# fanmonitor.net
KiCad netlist of a schematic drawn in EAGLE
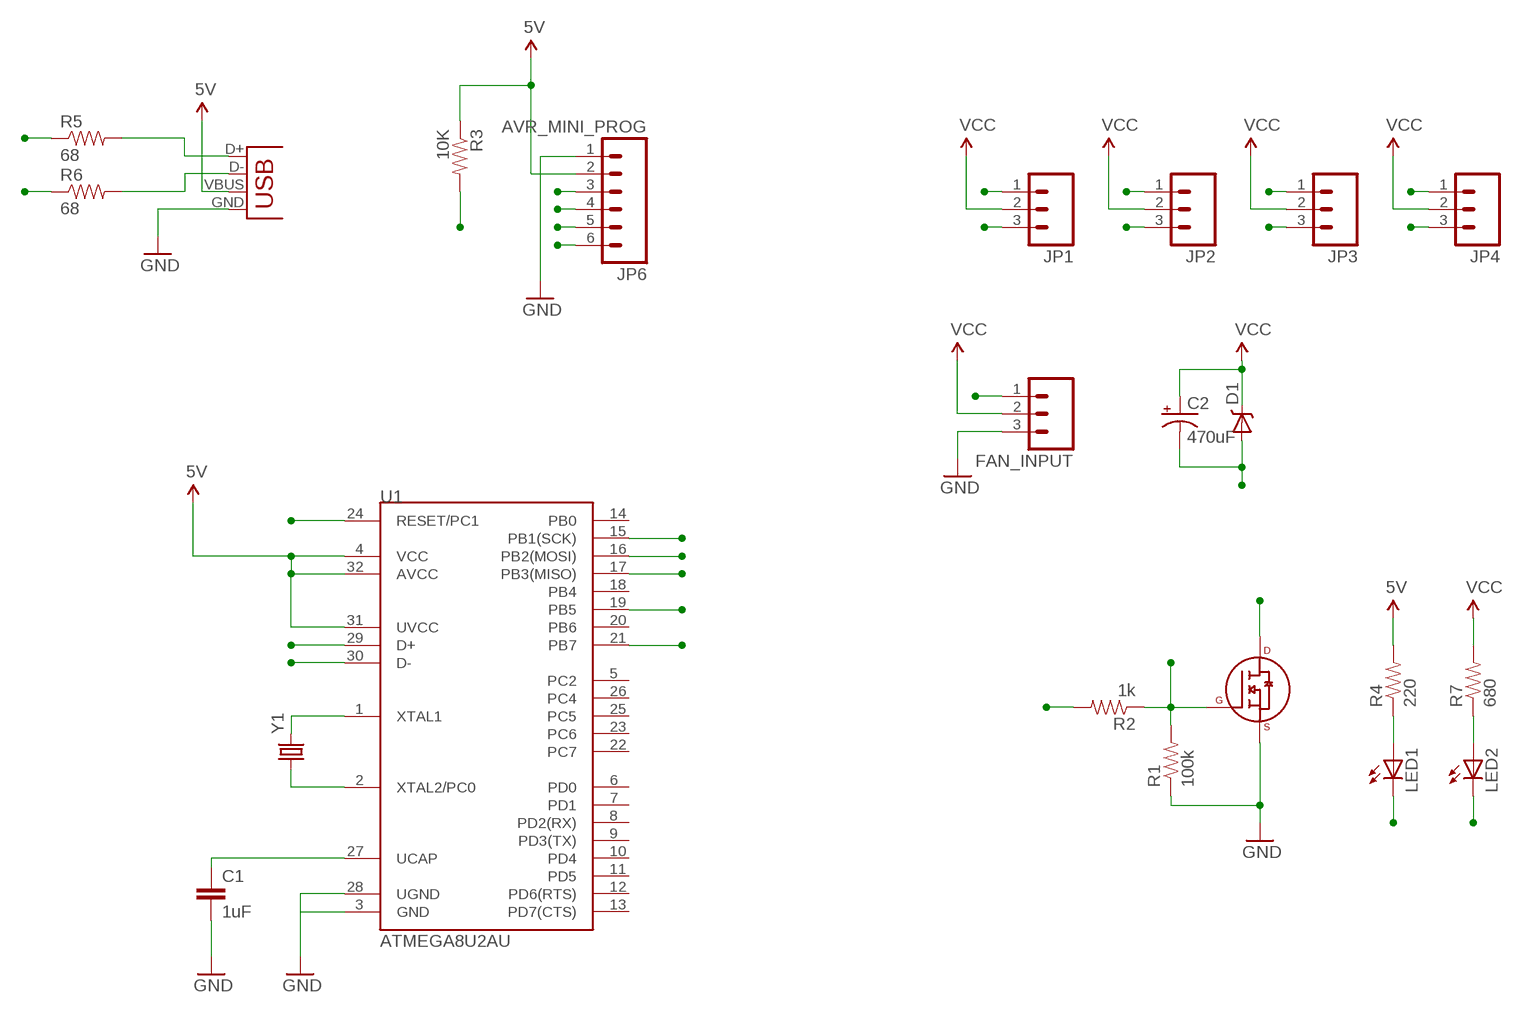
[diagram p0: schematic, sheet 1]

(export (version "E")
  (design (tool "Eeschema 10.0.6"))
  (components
    (comp (ref "C1")
      (value "1uF")
      (footprint "eagle-import:0603-CAP")
      (libsource (lib "eagle-import") (part "CAP0603-CAP"))
    )
    (comp (ref "C2")
      (value "470uF")
      (footprint "eagle-import:PANASONIC_D")
      (libsource (lib "eagle-import") (part "CAP_POLD"))
    )
    (comp (ref "D1")
      (value "DIODE-SCHOTTKY_")
      (footprint "eagle-import:SMA-DIODE")
      (libsource (lib "eagle-import") (part "DIODE-SCHOTTKY_"))
    )
    (comp (ref "FAN_INPUT")
      (value "M03PTH")
      (footprint "eagle-import:1X03")
      (libsource (lib "eagle-import") (part "M03PTH"))
    )
    (comp (ref "JP1")
      (value "M03PTH")
      (footprint "eagle-import:1X03")
      (libsource (lib "eagle-import") (part "M03PTH"))
    )
    (comp (ref "JP2")
      (value "M03PTH")
      (footprint "eagle-import:1X03")
      (libsource (lib "eagle-import") (part "M03PTH"))
    )
    (comp (ref "JP3")
      (value "M03PTH")
      (footprint "eagle-import:1X03")
      (libsource (lib "eagle-import") (part "M03PTH"))
    )
    (comp (ref "JP4")
      (value "M03PTH")
      (footprint "eagle-import:1X03")
      (libsource (lib "eagle-import") (part "M03PTH"))
    )
    (comp (ref "JP6")
      (value "AVR_MINI_PROG")
      (footprint "eagle-import:1X06")
      (libsource (lib "eagle-import") (part "M06SIP"))
    )
    (comp (ref "LED1")
      (value "LED0603")
      (footprint "eagle-import:LED-0603")
      (libsource (lib "eagle-import") (part "LED0603"))
    )
    (comp (ref "LED2")
      (value "LED0603")
      (footprint "eagle-import:LED-0603")
      (libsource (lib "eagle-import") (part "LED0603"))
    )
    (comp (ref "R1")
      (value "100k")
      (footprint "eagle-import:0603-RES")
      (libsource (lib "eagle-import") (part "RESISTOR0603-RES"))
    )
    (comp (ref "R2")
      (value "1k")
      (footprint "eagle-import:0603-RES")
      (libsource (lib "eagle-import") (part "RESISTOR0603-RES"))
    )
    (comp (ref "R3")
      (value "10K")
      (footprint "eagle-import:0603-RES")
      (libsource (lib "eagle-import") (part "RESISTOR0603-RES"))
    )
    (comp (ref "R4")
      (value "220")
      (footprint "eagle-import:0603-RES")
      (libsource (lib "eagle-import") (part "RESISTOR0603-RES"))
    )
    (comp (ref "R5")
      (value "68")
      (footprint "eagle-import:0603-RES")
      (libsource (lib "eagle-import") (part "RESISTOR0603-RES"))
    )
    (comp (ref "R6")
      (value "68")
      (footprint "eagle-import:0603-RES")
      (libsource (lib "eagle-import") (part "RESISTOR0603-RES"))
    )
    (comp (ref "R7")
      (value "680")
      (footprint "eagle-import:0603-RES")
      (libsource (lib "eagle-import") (part "RESISTOR0603-RES"))
    )
    (comp (ref "U$4")
      (value "RFD14N05L")
      (footprint "eagle-import:TO-252AA")
      (libsource (lib "eagle-import") (part "RFD14N05L"))
    )
    (comp (ref "U1")
      (value "ATMEGA8U2AU")
      (footprint "eagle-import:TQFP32-08")
      (libsource (lib "eagle-import") (part "ATMEGA8U2AU"))
    )
    (comp (ref "X1")
      (value "USBSMD")
      (footprint "eagle-import:USB-MINIB")
      (libsource (lib "eagle-import") (part "USBSMD"))
    )
    (comp (ref "Y1")
      (value "CRYSTAL5X3")
      (footprint "eagle-import:CRYSTAL-SMD-5X3")
      (libsource (lib "eagle-import") (part "CRYSTAL5X3"))
    )
  )
  (nets
    (net (code "1") (name "/D+") (class "Default")
      (node (ref "R5") (pin "1") (pinfunction "1_1") (pintype "passive"))
      (node (ref "U1") (pin "29") (pinfunction "D+_29") (pintype "bidirectional"))
    )
    (net (code "2") (name "/D-") (class "Default")
      (node (ref "R6") (pin "1") (pinfunction "1_1") (pintype "passive"))
      (node (ref "U1") (pin "30") (pinfunction "D-_30") (pintype "bidirectional"))
    )
    (net (code "3") (name "/MISO") (class "Default")
      (node (ref "JP6") (pin "3") (pinfunction "3_3") (pintype "passive"))
      (node (ref "U1") (pin "17") (pinfunction "PB3(MISO)_17") (pintype "bidirectional"))
    )
    (net (code "4") (name "/MOSI") (class "Default")
      (node (ref "JP6") (pin "6") (pinfunction "6_6") (pintype "passive"))
      (node (ref "U1") (pin "16") (pinfunction "PB2(MOSI)_16") (pintype "bidirectional"))
    )
    (net (code "5") (name "/PWM") (class "Default")
      (node (ref "FAN_INPUT") (pin "1") (pinfunction "1_1") (pintype "passive"))
      (node (ref "R2") (pin "2") (pinfunction "2_2") (pintype "passive"))
      (node (ref "U1") (pin "21") (pinfunction "PB7_21") (pintype "bidirectional"))
    )
    (net (code "6") (name "/PWM_OUT") (class "Default")
      (node (ref "C2") (pin "-") (pinfunction "-_-") (pintype "passive"))
      (node (ref "D1") (pin "A") (pinfunction "A_A") (pintype "passive"))
      (node (ref "JP1") (pin "3") (pinfunction "3_3") (pintype "passive"))
      (node (ref "JP2") (pin "3") (pinfunction "3_3") (pintype "passive"))
      (node (ref "JP3") (pin "3") (pinfunction "3_3") (pintype "passive"))
      (node (ref "JP4") (pin "3") (pinfunction "3_3") (pintype "passive"))
      (node (ref "LED2") (pin "C") (pinfunction "C_C") (pintype "passive"))
      (node (ref "U$4") (pin "4") (pinfunction "D_4") (pintype "bidirectional"))
    )
    (net (code "7") (name "/SCK") (class "Default")
      (node (ref "JP6") (pin "4") (pinfunction "4_4") (pintype "passive"))
      (node (ref "U1") (pin "15") (pinfunction "PB1(SCK)_15") (pintype "bidirectional"))
    )
    (net (code "8") (name "/STAT") (class "Default")
      (node (ref "LED1") (pin "C") (pinfunction "C_C") (pintype "passive"))
      (node (ref "U1") (pin "19") (pinfunction "PB5_19") (pintype "bidirectional"))
    )
    (net (code "9") (name "/{slash}RST") (class "Default")
      (node (ref "JP6") (pin "5") (pinfunction "5_5") (pintype "passive"))
      (node (ref "R3") (pin "2") (pinfunction "2_2") (pintype "passive"))
      (node (ref "U1") (pin "24") (pinfunction "RESET/PC1_24") (pintype "bidirectional"))
    )
    (net (code "10") (name "5V") (class "Default")
      (node (ref "JP6") (pin "2") (pinfunction "2_2") (pintype "passive"))
      (node (ref "R3") (pin "1") (pinfunction "1_1") (pintype "passive"))
      (node (ref "R4") (pin "2") (pinfunction "2_2") (pintype "passive"))
      (node (ref "U1") (pin "31") (pinfunction "UVCC_31") (pintype "bidirectional"))
      (node (ref "U1") (pin "32") (pinfunction "AVCC_32") (pintype "bidirectional"))
      (node (ref "U1") (pin "4") (pinfunction "VCC_4") (pintype "bidirectional"))
      (node (ref "X1") (pin "VBUS") (pinfunction "VBUS_VBUS") (pintype "bidirectional"))
    )
    (net (code "11") (name "GND") (class "Default")
      (node (ref "C1") (pin "2") (pinfunction "2_2") (pintype "passive"))
      (node (ref "FAN_INPUT") (pin "3") (pinfunction "3_3") (pintype "passive"))
      (node (ref "JP1") (pin "1") (pinfunction "1_1") (pintype "passive"))
      (node (ref "JP2") (pin "1") (pinfunction "1_1") (pintype "passive"))
      (node (ref "JP3") (pin "1") (pinfunction "1_1") (pintype "passive"))
      (node (ref "JP4") (pin "1") (pinfunction "1_1") (pintype "passive"))
      (node (ref "JP6") (pin "1") (pinfunction "1_1") (pintype "passive"))
      (node (ref "R1") (pin "1") (pinfunction "1_1") (pintype "passive"))
      (node (ref "U$4") (pin "3") (pinfunction "S_3") (pintype "bidirectional"))
      (node (ref "U1") (pin "28") (pinfunction "UGND_28") (pintype "bidirectional"))
      (node (ref "U1") (pin "3") (pinfunction "GND_3") (pintype "bidirectional"))
      (node (ref "X1") (pin "GND") (pinfunction "GND_GND") (pintype "bidirectional"))
    )
    (net (code "12") (name "Net-(LED1-PadA)") (class "Default")
      (node (ref "LED1") (pin "A") (pinfunction "A_A") (pintype "passive"))
      (node (ref "R4") (pin "1") (pinfunction "1_1") (pintype "passive"))
    )
    (net (code "13") (name "Net-(LED2-PadA)") (class "Default")
      (node (ref "LED2") (pin "A") (pinfunction "A_A") (pintype "passive"))
      (node (ref "R7") (pin "1") (pinfunction "1_1") (pintype "passive"))
    )
    (net (code "14") (name "Net-(R5-Pad2)") (class "Default")
      (node (ref "R5") (pin "2") (pinfunction "2_2") (pintype "passive"))
      (node (ref "X1") (pin "D+") (pinfunction "D+_D+") (pintype "bidirectional"))
    )
    (net (code "15") (name "Net-(R6-Pad2)") (class "Default")
      (node (ref "R6") (pin "2") (pinfunction "2_2") (pintype "passive"))
      (node (ref "X1") (pin "D-") (pinfunction "D-_D-") (pintype "bidirectional"))
    )
    (net (code "16") (name "Net-(U$4-G)") (class "Default")
      (node (ref "R1") (pin "2") (pinfunction "2_2") (pintype "passive"))
      (node (ref "R2") (pin "1") (pinfunction "1_1") (pintype "passive"))
      (node (ref "U$4") (pin "1") (pinfunction "G_1") (pintype "bidirectional"))
    )
    (net (code "17") (name "Net-(U1-UCAP)") (class "Default")
      (node (ref "C1") (pin "1") (pinfunction "1_1") (pintype "passive"))
      (node (ref "U1") (pin "27") (pinfunction "UCAP_27") (pintype "bidirectional"))
    )
    (net (code "18") (name "Net-(U1-XTAL1)") (class "Default")
      (node (ref "U1") (pin "1") (pinfunction "XTAL1_1") (pintype "bidirectional"))
      (node (ref "Y1") (pin "3") (pinfunction "2_3") (pintype "passive"))
    )
    (net (code "19") (name "Net-(U1-XTAL2{slash}PC0)") (class "Default")
      (node (ref "U1") (pin "2") (pinfunction "XTAL2/PC0_2") (pintype "bidirectional"))
      (node (ref "Y1") (pin "1") (pinfunction "1_1") (pintype "passive"))
    )
    (net (code "20") (name "VCC") (class "Default")
      (node (ref "C2") (pin "+") (pinfunction "+_+") (pintype "passive"))
      (node (ref "D1") (pin "C") (pinfunction "C_C") (pintype "passive"))
      (node (ref "FAN_INPUT") (pin "2") (pinfunction "2_2") (pintype "passive"))
      (node (ref "JP1") (pin "2") (pinfunction "2_2") (pintype "passive"))
      (node (ref "JP2") (pin "2") (pinfunction "2_2") (pintype "passive"))
      (node (ref "JP3") (pin "2") (pinfunction "2_2") (pintype "passive"))
      (node (ref "JP4") (pin "2") (pinfunction "2_2") (pintype "passive"))
      (node (ref "R7") (pin "2") (pinfunction "2_2") (pintype "passive"))
    )
    (net (code "21") (name "unconnected-(U1-PB0-Pad14)") (class "Default")
      (node (ref "U1") (pin "14") (pinfunction "PB0_14") (pintype "bidirectional"))
    )
    (net (code "22") (name "unconnected-(U1-PB4-Pad18)") (class "Default")
      (node (ref "U1") (pin "18") (pinfunction "PB4_18") (pintype "bidirectional"))
    )
    (net (code "23") (name "unconnected-(U1-PB6-Pad20)") (class "Default")
      (node (ref "U1") (pin "20") (pinfunction "PB6_20") (pintype "bidirectional"))
    )
    (net (code "24") (name "unconnected-(U1-PC2-Pad5)") (class "Default")
      (node (ref "U1") (pin "5") (pinfunction "PC2_5") (pintype "bidirectional"))
    )
    (net (code "25") (name "unconnected-(U1-PC4-Pad26)") (class "Default")
      (node (ref "U1") (pin "26") (pinfunction "PC4_26") (pintype "bidirectional"))
    )
    (net (code "26") (name "unconnected-(U1-PC5-Pad25)") (class "Default")
      (node (ref "U1") (pin "25") (pinfunction "PC5_25") (pintype "bidirectional"))
    )
    (net (code "27") (name "unconnected-(U1-PC6-Pad23)") (class "Default")
      (node (ref "U1") (pin "23") (pinfunction "PC6_23") (pintype "bidirectional"))
    )
    (net (code "28") (name "unconnected-(U1-PC7-Pad22)") (class "Default")
      (node (ref "U1") (pin "22") (pinfunction "PC7_22") (pintype "bidirectional"))
    )
    (net (code "29") (name "unconnected-(U1-PD0-Pad6)") (class "Default")
      (node (ref "U1") (pin "6") (pinfunction "PD0_6") (pintype "bidirectional"))
    )
    (net (code "30") (name "unconnected-(U1-PD1-Pad7)") (class "Default")
      (node (ref "U1") (pin "7") (pinfunction "PD1_7") (pintype "bidirectional"))
    )
    (net (code "31") (name "unconnected-(U1-PD2(RX)-Pad8)") (class "Default")
      (node (ref "U1") (pin "8") (pinfunction "PD2(RX)_8") (pintype "bidirectional"))
    )
    (net (code "32") (name "unconnected-(U1-PD3(TX)-Pad9)") (class "Default")
      (node (ref "U1") (pin "9") (pinfunction "PD3(TX)_9") (pintype "bidirectional"))
    )
    (net (code "33") (name "unconnected-(U1-PD4-Pad10)") (class "Default")
      (node (ref "U1") (pin "10") (pinfunction "PD4_10") (pintype "bidirectional"))
    )
    (net (code "34") (name "unconnected-(U1-PD5-Pad11)") (class "Default")
      (node (ref "U1") (pin "11") (pinfunction "PD5_11") (pintype "bidirectional"))
    )
    (net (code "35") (name "unconnected-(U1-PD6(RTS)-Pad12)") (class "Default")
      (node (ref "U1") (pin "12") (pinfunction "PD6(RTS)_12") (pintype "bidirectional"))
    )
    (net (code "36") (name "unconnected-(U1-PD7(CTS)-Pad13)") (class "Default")
      (node (ref "U1") (pin "13") (pinfunction "PD7(CTS)_13") (pintype "bidirectional"))
    )
  )
)
